# Shining_Pig_9V.net
KiCad netlist of a schematic drawn in Altium Designer
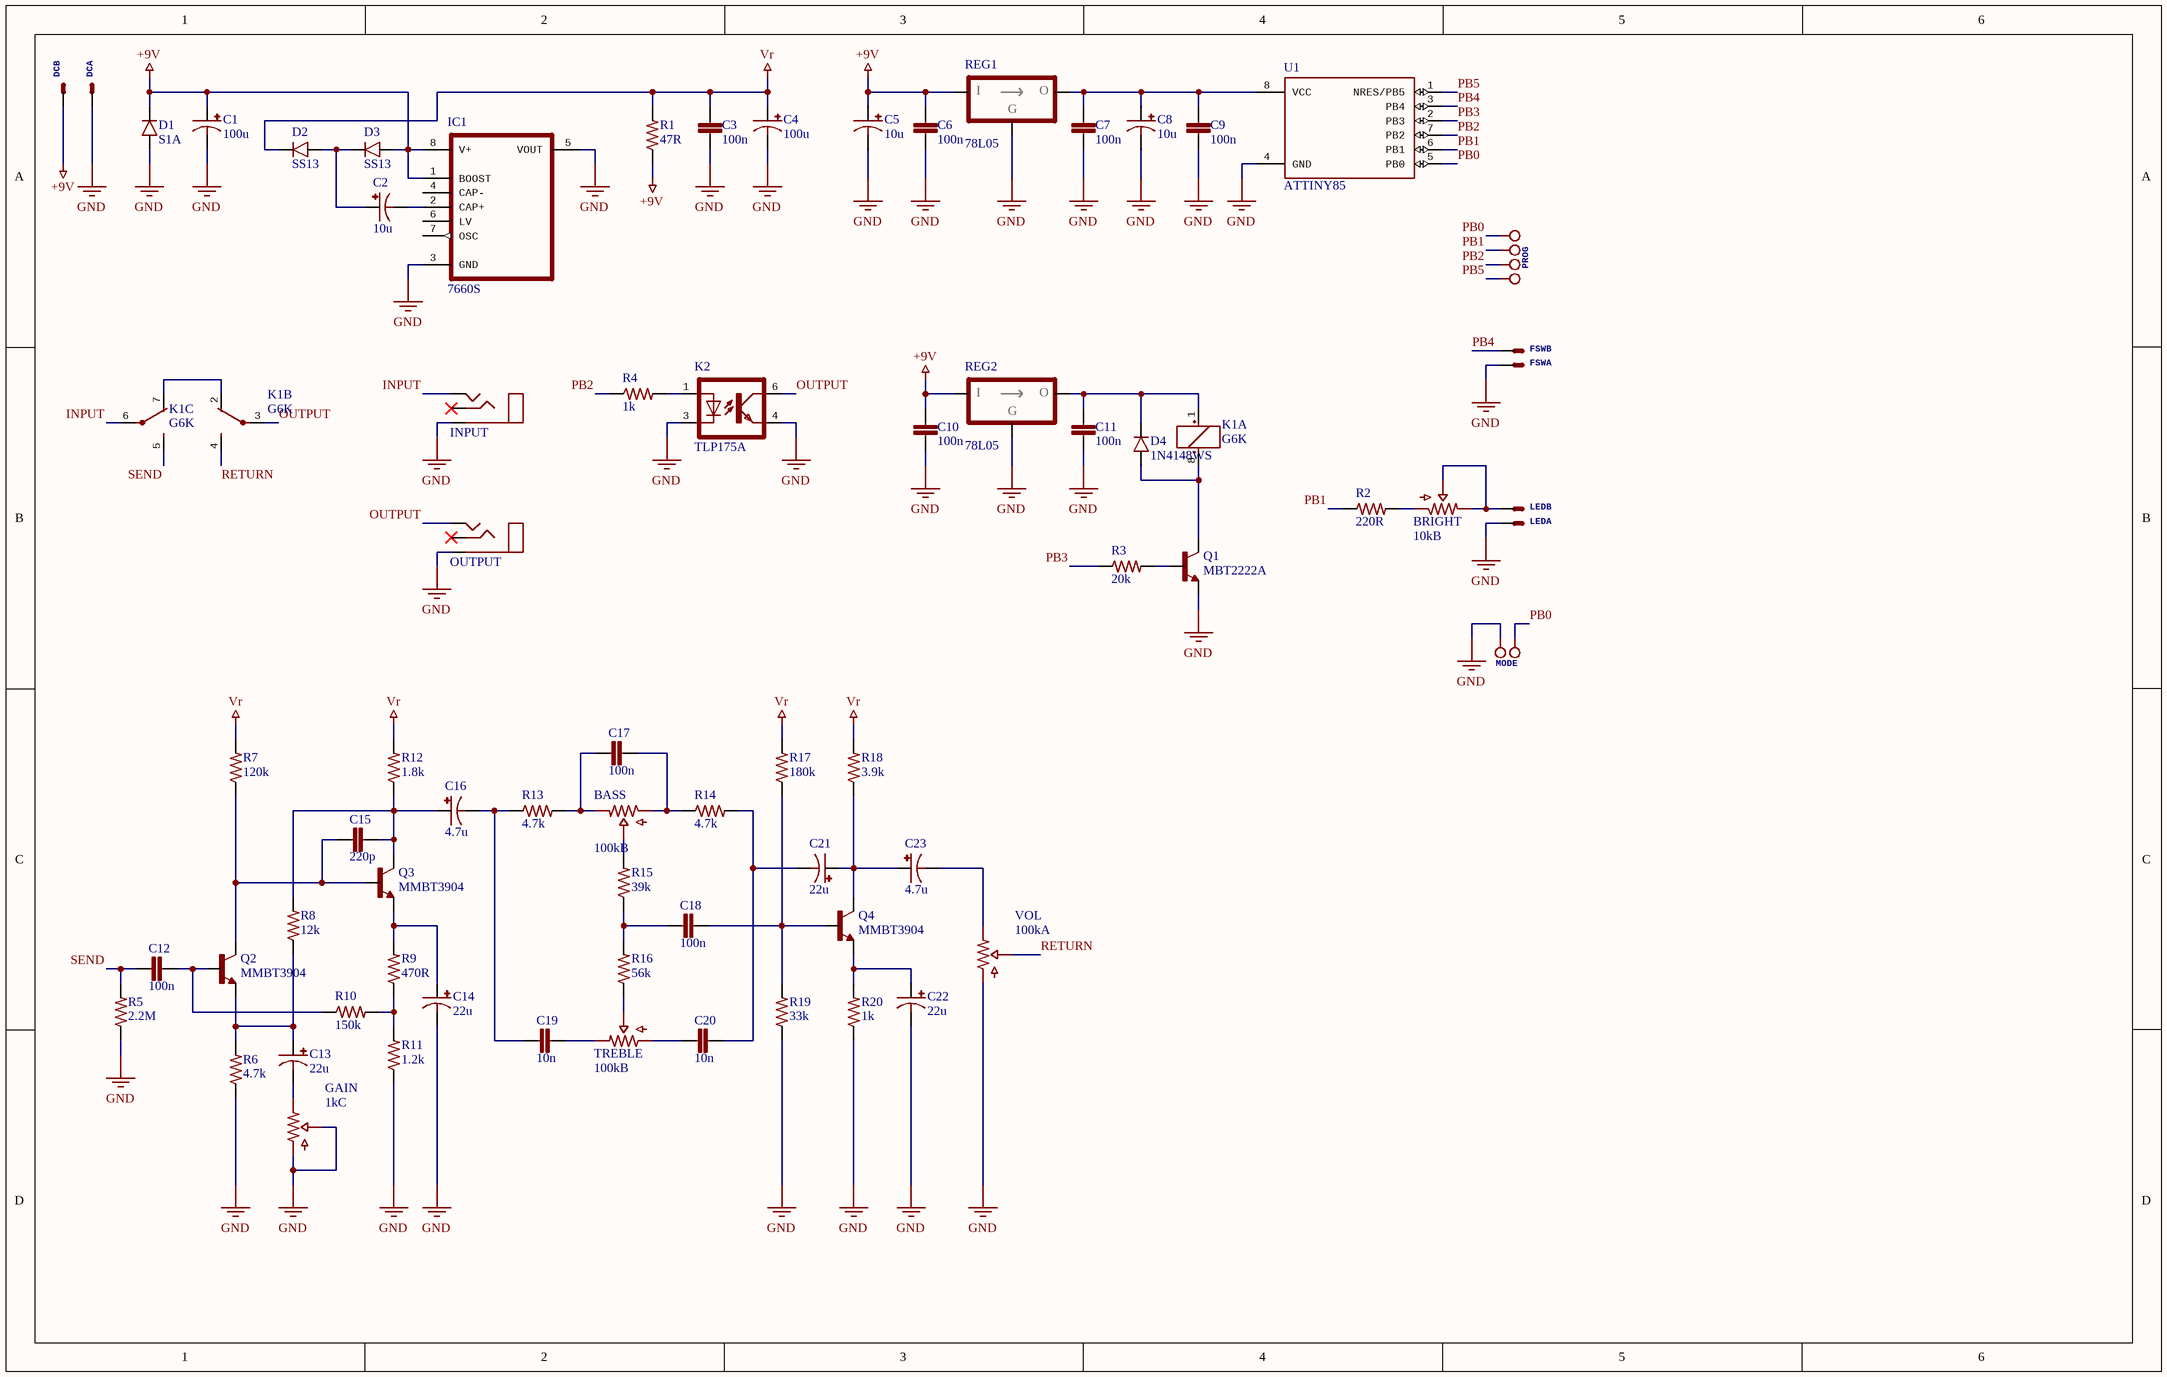
[diagram p0: Shining Pig 9V.SchDoc]

(export (version "E")
  (design (tool "Eeschema 10.0.6"))
  (components
    (comp (ref "BASS")
      (value "100kB")
      (footprint "ALPHA_16mm_BOTTOM")
      (description "100k Lin potentiometer round shaft")
      (libsource (lib "Pedals") (part "POT_100kB_ALPHA_16mm"))
    )
    (comp (ref "BRIGHT")
      (value "10kB")
      (footprint "BOURNS_3362P")
      (description "10k Lin 3362P trimmer")
      (libsource (lib "Pedals") (part "TRIM_10kB_3362P"))
    )
    (comp (ref "C1")
      (value "100u")
      (footprint "CAPAE_D")
      (description "CAP ALUM 100UF 25V SMD")
      (fields
        (field (name "MANUFACTURER") "Multicomp")
        (field (name "MANUFACTURER PART NUMBER") "MCVVT025M101EA6L")
      )
      (libsource (lib "Pedals SMD") (part "MCVVT025M101EA6L"))
    )
    (comp (ref "C2")
      (value "10u")
      (footprint "CAPAE_B")
      (description "CAP ALUM 10UF 25V SMD")
      (fields
        (field (name "MANUFACTURER") "Multicomp")
        (field (name "MANUFACTURER PART NUMBER") "MCVVT025M100CA1L")
      )
      (libsource (lib "") (part "MCVVT025M100CA1L_1"))
    )
    (comp (ref "C3")
      (value "100n")
      (footprint "CHIP_0603")
      (description "CAP CER 100NF 50V X7R 0603")
      (fields
        (field (name "MANUFACTURER") "Multicomp")
        (field (name "MANUFACTURER PART NUMBER") "MC0603B104K500CT")
      )
      (libsource (lib "Pedals SMD") (part "MC0603B104K500CT"))
    )
    (comp (ref "C4")
      (value "100u")
      (footprint "CAPAE_D")
      (description "CAP ALUM 100UF 25V SMD")
      (fields
        (field (name "MANUFACTURER") "Multicomp")
        (field (name "MANUFACTURER PART NUMBER") "MCVVT025M101EA6L")
      )
      (libsource (lib "Pedals SMD") (part "MCVVT025M101EA6L"))
    )
    (comp (ref "C5")
      (value "10u")
      (footprint "CAPAE_B")
      (description "CAP ALUM 10UF 25V SMD")
      (fields
        (field (name "MANUFACTURER") "Multicomp")
        (field (name "MANUFACTURER PART NUMBER") "MCVVT025M100CA1L")
      )
      (libsource (lib "Pedals SMD") (part "MCVVT025M100CA1L"))
    )
    (comp (ref "C6")
      (value "100n")
      (footprint "CHIP_0603")
      (description "CAP CER 100NF 50V X7R 0603")
      (fields
        (field (name "MANUFACTURER") "Multicomp")
        (field (name "MANUFACTURER PART NUMBER") "MC0603B104K500CT")
      )
      (libsource (lib "Pedals SMD") (part "MC0603B104K500CT"))
    )
    (comp (ref "C7")
      (value "100n")
      (footprint "CHIP_0603")
      (description "CAP CER 100NF 50V X7R 0603")
      (fields
        (field (name "MANUFACTURER") "Multicomp")
        (field (name "MANUFACTURER PART NUMBER") "MC0603B104K500CT")
      )
      (libsource (lib "Pedals SMD") (part "MC0603B104K500CT"))
    )
    (comp (ref "C8")
      (value "10u")
      (footprint "CAPAE_B")
      (description "CAP ALUM 10UF 25V SMD")
      (fields
        (field (name "MANUFACTURER") "Multicomp")
        (field (name "MANUFACTURER PART NUMBER") "MCVVT025M100CA1L")
      )
      (libsource (lib "Pedals SMD") (part "MCVVT025M100CA1L"))
    )
    (comp (ref "C9")
      (value "100n")
      (footprint "CHIP_0603")
      (description "CAP CER 100NF 50V X7R 0603")
      (fields
        (field (name "MANUFACTURER") "Multicomp")
        (field (name "MANUFACTURER PART NUMBER") "MC0603B104K500CT")
      )
      (libsource (lib "Pedals SMD") (part "MC0603B104K500CT"))
    )
    (comp (ref "C10")
      (value "100n")
      (footprint "CHIP_0603")
      (description "CAP CER 100NF 50V X7R 0603")
      (fields
        (field (name "MANUFACTURER") "Multicomp")
        (field (name "MANUFACTURER PART NUMBER") "MC0603B104K500CT")
      )
      (libsource (lib "Pedals SMD") (part "MC0603B104K500CT"))
    )
    (comp (ref "C11")
      (value "100n")
      (footprint "CHIP_0603")
      (description "CAP CER 100NF 50V X7R 0603")
      (fields
        (field (name "MANUFACTURER") "Multicomp")
        (field (name "MANUFACTURER PART NUMBER") "MC0603B104K500CT")
      )
      (libsource (lib "Pedals SMD") (part "MC0603B104K500CT"))
    )
    (comp (ref "C12")
      (value "100n")
      (footprint "CHIP_1206")
      (description "CAP CER 100NF 50V C0G/NP0 1206")
      (fields
        (field (name "MANUFACTURER") "Murata")
        (field (name "MANUFACTURER PART NUMBER") "GRM31C5C1H104JA01L")
      )
      (libsource (lib "Pedals SMD") (part "GRM31C5C1H104JA01L"))
    )
    (comp (ref "C13")
      (value "22u")
      (footprint "CAPAE_D")
      (description "CAP ALUM 22UF 20% 35V LESR SMD")
      (fields
        (field (name "MANUFACTURER") "Panasonic")
        (field (name "MANUFACTURER PART NUMBER") "EEEFC1V220AP")
      )
      (libsource (lib "Pedals SMD") (part "EEEFC1V220AP"))
    )
    (comp (ref "C14")
      (value "22u")
      (footprint "CAPAE_D")
      (description "CAP ALUM 22UF 20% 35V LESR SMD")
      (fields
        (field (name "MANUFACTURER") "Panasonic")
        (field (name "MANUFACTURER PART NUMBER") "EEEFC1V220AP")
      )
      (libsource (lib "Pedals SMD") (part "EEEFC1V220AP"))
    )
    (comp (ref "C15")
      (value "220p")
      (footprint "CHIP_0603")
      (description "CAP CER 220PF 50V C0G/NP0 0603")
      (fields
        (field (name "MANUFACTURER") "Multicomp")
        (field (name "MANUFACTURER PART NUMBER") "MC0603N221J500CT")
      )
      (libsource (lib "Pedals SMD") (part "MC0603N221J500CT"))
    )
    (comp (ref "C16")
      (value "4.7u")
      (footprint "CAPAE_C")
      (description "CAP ALUM 4.7UF 50V LESR SMD")
      (fields
        (field (name "MANUFACTURER") "Panasonic")
        (field (name "MANUFACTURER PART NUMBER") "EEEFC1H4R7R")
      )
      (libsource (lib "Pedals SMD") (part "EEEFC1H4R7R"))
    )
    (comp (ref "C17")
      (value "100n")
      (footprint "CHIP_1206")
      (description "CAP CER 100NF 50V C0G/NP0 1206")
      (fields
        (field (name "MANUFACTURER") "Murata")
        (field (name "MANUFACTURER PART NUMBER") "GRM31C5C1H104JA01L")
      )
      (libsource (lib "Pedals SMD") (part "GRM31C5C1H104JA01L"))
    )
    (comp (ref "C18")
      (value "100n")
      (footprint "CHIP_1206")
      (description "CAP CER 100NF 50V C0G/NP0 1206")
      (fields
        (field (name "MANUFACTURER") "Murata")
        (field (name "MANUFACTURER PART NUMBER") "GRM31C5C1H104JA01L")
      )
      (libsource (lib "Pedals SMD") (part "GRM31C5C1H104JA01L"))
    )
    (comp (ref "C19")
      (value "10n")
      (footprint "CHIP_0603")
      (description "CAP CER 10NF 50V C0G/NP0 0603")
      (fields
        (field (name "MANUFACTURER") "Murata")
        (field (name "MANUFACTURER PART NUMBER") "GRM1885C1H103JA01D")
      )
      (libsource (lib "Pedals SMD") (part "GRM1885C1H103JA01D"))
    )
    (comp (ref "C20")
      (value "10n")
      (footprint "CHIP_0603")
      (description "CAP CER 10NF 50V C0G/NP0 0603")
      (fields
        (field (name "MANUFACTURER") "Murata")
        (field (name "MANUFACTURER PART NUMBER") "GRM1885C1H103JA01D")
      )
      (libsource (lib "Pedals SMD") (part "GRM1885C1H103JA01D"))
    )
    (comp (ref "C21")
      (value "22u")
      (footprint "CAPAE_D")
      (description "CAP ALUM 22UF 20% 35V LESR SMD")
      (fields
        (field (name "MANUFACTURER") "Panasonic")
        (field (name "MANUFACTURER PART NUMBER") "EEEFC1V220AP")
      )
      (libsource (lib "") (part "EEEFC1V220AP_1"))
    )
    (comp (ref "C22")
      (value "22u")
      (footprint "CAPAE_D")
      (description "CAP ALUM 22UF 20% 35V LESR SMD")
      (fields
        (field (name "MANUFACTURER") "Panasonic")
        (field (name "MANUFACTURER PART NUMBER") "EEEFC1V220AP")
      )
      (libsource (lib "Pedals SMD") (part "EEEFC1V220AP"))
    )
    (comp (ref "C23")
      (value "4.7u")
      (footprint "CAPAE_C")
      (description "CAP ALUM 4.7UF 50V LESR SMD")
      (fields
        (field (name "MANUFACTURER") "Panasonic")
        (field (name "MANUFACTURER PART NUMBER") "EEEFC1H4R7R")
      )
      (libsource (lib "Pedals SMD") (part "EEEFC1H4R7R"))
    )
    (comp (ref "D1")
      (value "S1A")
      (footprint "DO214")
      (description "DIODE GEN PURP 50V 1A SMA")
      (fields (field (name "MANUFACTURER") "ON Semiconductor / Fairchild"))
      (libsource (lib "Pedals SMD") (part "S1A"))
    )
    (comp (ref "D2")
      (value "SS13")
      (footprint "SOD123F")
      (description "DIODE SCHOTTKY 30V 1A SOD123F")
      (fields
        (field (name "MANUFACTURER") "ON Semiconductor / Fairchild")
        (field (name "MANUFACTURER PART NUMBER") "SS13FL")
      )
      (libsource (lib "Pedals SMD") (part "SS13FL"))
    )
    (comp (ref "D3")
      (value "SS13")
      (footprint "SOD123F")
      (description "DIODE SCHOTTKY 30V 1A SOD123F")
      (fields
        (field (name "MANUFACTURER") "ON Semiconductor / Fairchild")
        (field (name "MANUFACTURER PART NUMBER") "SS13FL")
      )
      (libsource (lib "Pedals SMD") (part "SS13FL"))
    )
    (comp (ref "D4")
      (value "1N4148WS")
      (footprint "SOD323")
      (description "DIODE GEN PURP 75V 150MA SOD323F")
      (fields (field (name "MANUFACTURER") "ON Semiconductor / Fairchild"))
      (libsource (lib "Pedals SMD") (part "1N4148WS"))
    )
    (comp (ref "DC")
      (value "J_JST-XH-02")
      (footprint "JST-XH-02")
      (description "2 Pins male XH header")
      (libsource (lib "Pedals") (part "J_JST-XH-02"))
    )
    (comp (ref "FSW")
      (value "J_JST-XH-02")
      (footprint "JST-XH-02")
      (description "2 Pins male XH header")
      (libsource (lib "Pedals") (part "J_JST-XH-02"))
    )
    (comp (ref "GAIN")
      (value "1kC")
      (footprint "ALPHA_16mm_BOTTOM")
      (description "1k Reverse log potentiometer round shaft")
      (libsource (lib "Pedals") (part "POT_1kC_ALPHA_16mm"))
    )
    (comp (ref "IC1")
      (value "7660S")
      (footprint "SO8")
      (description "RENESAS - ICL7660SCBAZ - IC DC DC CHARGE PUMP")
      (fields
        (field (name "MANUFACTURER") "Intersil")
        (field (name "MANUFACTURER PART NUMBER") "ICL7660SCBAZ")
      )
      (libsource (lib "Pedals SMD") (part "ICL7660SCBAZ"))
    )
    (comp (ref "INPUT")
      (value "J_STEREO")
      (footprint "STEREO")
      (description "6.35mm stereo insulated socket jack PCB mounted")
      (libsource (lib "Pedals") (part "J_STEREO"))
    )
    (comp (ref "K1")
      (value "G6K")
      (footprint "G6K")
      (description "OMRON - G6K-2F 5DC - RELAY, SIGNAL, DPDT, 30VDC, 1A")
      (fields (field (name "MANUFACTURER") "Cliff") (field (name "MANUFACTURER PART NUMBER") "G6K-2F5DC"))
      (libsource (lib "") (part "G6K-2F5DC_1"))
    )
    (comp (ref "K2")
      (value "TLP175A")
      (footprint "TLP175A")
      (description "Toshiba TLP175A AC Input MOSFET Output Optocoupler, Surface Mount, 4-Pin SOIC")
      (fields (field (name "MANUFACTURER") "Toshiba"))
      (libsource (lib "Pedals SMD") (part "TLP175A"))
    )
    (comp (ref "LED")
      (value "J_JST-XH-02")
      (footprint "JST-XH-02")
      (description "2 Pins male XH header")
      (libsource (lib "Pedals") (part "J_JST-XH-02"))
    )
    (comp (ref "MODE")
      (value "J_HEADER_2PINS")
      (footprint "HEADER_2PINS")
      (description "2 Pins male header")
      (libsource (lib "Pedals") (part "J_HEADER_2PINS"))
    )
    (comp (ref "OUTPUT")
      (value "J_STEREO")
      (footprint "STEREO")
      (description "6.35mm stereo insulated socket jack PCB mounted")
      (libsource (lib "Pedals") (part "J_STEREO"))
    )
    (comp (ref "PROG")
      (value "J_HEADER_4PINS_FEM")
      (footprint "HEADER_4Pins_FEM")
      (description "4 Pins female header")
      (libsource (lib "Pedals") (part "J_HEADER_4PINS_FEM"))
    )
    (comp (ref "Q1")
      (value "MBT2222A")
      (footprint "SOT323")
      (description "TRANS NPN 40V 0.6A SOT323")
      (fields
        (field (name "MANUFACTURER") "ON Semiconductor")
        (field (name "MANUFACTURER PART NUMBER") "MMBT2222AWT1G")
      )
      (libsource (lib "Pedals SMD") (part "MMBT2222AWT1G"))
    )
    (comp (ref "Q2")
      (value "MMBT3904")
      (footprint "SOT23")
      (description "TRANS NPN 40V 0.2A SOT23")
      (fields
        (field (name "MANUFACTURER") "ON Semiconductor")
        (field (name "MANUFACTURER PART NUMBER") "MMBT3904LT1G")
      )
      (libsource (lib "Pedals SMD") (part "MMBT3904LT1G"))
    )
    (comp (ref "Q3")
      (value "MMBT3904")
      (footprint "SOT23")
      (description "TRANS NPN 40V 0.2A SOT23")
      (fields
        (field (name "MANUFACTURER") "ON Semiconductor")
        (field (name "MANUFACTURER PART NUMBER") "MMBT3904LT1G")
      )
      (libsource (lib "Pedals SMD") (part "MMBT3904LT1G"))
    )
    (comp (ref "Q4")
      (value "MMBT3904")
      (footprint "SOT23")
      (description "TRANS NPN 40V 0.2A SOT23")
      (fields
        (field (name "MANUFACTURER") "ON Semiconductor")
        (field (name "MANUFACTURER PART NUMBER") "MMBT3904LT1G")
      )
      (libsource (lib "Pedals SMD") (part "MMBT3904LT1G"))
    )
    (comp (ref "R1")
      (value "47R")
      (footprint "CHIP_R_1206")
      (description "RES SMD 47 OHM 1% 1/4W 1206")
      (fields
        (field (name "MANUFACTURER") "Vishay")
        (field (name "MANUFACTURER PART NUMBER") "CRCW120647R0FKEA")
      )
      (libsource (lib "Pedals SMD") (part "CRCW120647R0FKEA"))
    )
    (comp (ref "R2")
      (value "220R")
      (footprint "CHIP_R_1206")
      (description "RES SMD 220 OHM 1% 1/4W 1206")
      (fields
        (field (name "MANUFACTURER") "Vishay")
        (field (name "MANUFACTURER PART NUMBER") "CRCW1206220RFKEA")
      )
      (libsource (lib "Pedals SMD") (part "CRCW1206220RFKEA"))
    )
    (comp (ref "R3")
      (value "20k")
      (footprint "CHIP_R_0603")
      (description "RES SMD 20K OHM 1% 1/10W 0603")
      (fields
        (field (name "MANUFACTURER") "Vishay")
        (field (name "MANUFACTURER PART NUMBER") "CRCW060320K0FKEA")
      )
      (libsource (lib "Pedals SMD") (part "CRCW060320K0FKEA"))
    )
    (comp (ref "R4")
      (value "1k")
      (footprint "CHIP_R_0603")
      (description "RES SMD 1K OHM 1% 1/10W 0603")
      (fields
        (field (name "MANUFACTURER") "Vishay Dale")
        (field (name "MANUFACTURER PART NUMBER") "CRCW06031K00FKEA")
      )
      (libsource (lib "Pedals SMD") (part "CRCW06031K00FKEA"))
    )
    (comp (ref "R5")
      (value "2.2M")
      (footprint "CHIP_R_0603")
      (description "RES SMD 2.2M OHM 1% 1/10W 0603")
      (fields
        (field (name "MANUFACTURER") "Vishay")
        (field (name "MANUFACTURER PART NUMBER") "CRCW06032M20FKEA")
      )
      (libsource (lib "Pedals SMD") (part "CRCW06032M20FKEA"))
    )
    (comp (ref "R6")
      (value "4.7k")
      (footprint "CHIP_R_0603")
      (description "RES SMD 4.7K OHM 1% 1/10W 0603")
      (fields
        (field (name "MANUFACTURER") "Vishay")
        (field (name "MANUFACTURER PART NUMBER") "CRCW06034K70FKEA")
      )
      (libsource (lib "Pedals SMD") (part "CRCW06034K70FKEA"))
    )
    (comp (ref "R7")
      (value "120k")
      (footprint "CHIP_R_1206")
      (description "RES SMD 120K OHM 1% 1/4W 1206")
      (fields
        (field (name "MANUFACTURER") "Vishay")
        (field (name "MANUFACTURER PART NUMBER") "CRCW1206120KFKEA")
      )
      (libsource (lib "Pedals SMD") (part "CRCW1206120KFKEA"))
    )
    (comp (ref "R8")
      (value "12k")
      (footprint "CHIP_R_0603")
      (description "RES SMD 12K OHM 1% 1/10W 0603")
      (fields
        (field (name "MANUFACTURER") "Vishay")
        (field (name "MANUFACTURER PART NUMBER") "CRCW060312K0FKEA")
      )
      (libsource (lib "Pedals SMD") (part "CRCW060312K0FKEA"))
    )
    (comp (ref "R9")
      (value "470R")
      (footprint "CHIP_R_0603")
      (description "RES SMD 470 OHM 1% 1/10W 0603")
      (fields
        (field (name "MANUFACTURER") "Vishay")
        (field (name "MANUFACTURER PART NUMBER") "CRCW0603470RFKEA")
      )
      (libsource (lib "Pedals SMD") (part "CRCW0603470RFKEA"))
    )
    (comp (ref "R10")
      (value "150k")
      (footprint "CHIP_R_0603")
      (description "RES SMD 150K OHM 1% 1/10W 0603")
      (fields
        (field (name "MANUFACTURER") "Vishay")
        (field (name "MANUFACTURER PART NUMBER") "CRCW0603150KFKEA")
      )
      (libsource (lib "Pedals SMD") (part "CRCW0603150KFKEA"))
    )
    (comp (ref "R11")
      (value "1.2k")
      (footprint "CHIP_R_0603")
      (description "RES SMD 1.2K OHM 1% 1/10W 0603")
      (fields
        (field (name "MANUFACTURER") "Vishay")
        (field (name "MANUFACTURER PART NUMBER") "CRCW06031K20FKEA")
      )
      (libsource (lib "Pedals SMD") (part "CRCW06031K20FKEA"))
    )
    (comp (ref "R12")
      (value "1.8k")
      (footprint "CHIP_R_1206")
      (description "RES SMD 1.8K OHM 1% 1/4W 1206")
      (fields
        (field (name "MANUFACTURER") "Vishay")
        (field (name "MANUFACTURER PART NUMBER") "CRCW12061K80FKEA")
      )
      (libsource (lib "Pedals SMD") (part "CRCW12061K80FKEA"))
    )
    (comp (ref "R13")
      (value "4.7k")
      (footprint "CHIP_R_0603")
      (description "RES SMD 4.7K OHM 1% 1/10W 0603")
      (fields
        (field (name "MANUFACTURER") "Vishay")
        (field (name "MANUFACTURER PART NUMBER") "CRCW06034K70FKEA")
      )
      (libsource (lib "Pedals SMD") (part "CRCW06034K70FKEA"))
    )
    (comp (ref "R14")
      (value "4.7k")
      (footprint "CHIP_R_0603")
      (description "RES SMD 4.7K OHM 1% 1/10W 0603")
      (fields
        (field (name "MANUFACTURER") "Vishay")
        (field (name "MANUFACTURER PART NUMBER") "CRCW06034K70FKEA")
      )
      (libsource (lib "Pedals SMD") (part "CRCW06034K70FKEA"))
    )
    (comp (ref "R15")
      (value "39k")
      (footprint "CHIP_R_0603")
      (description "RES SMD 39K OHM 1% 1/10W 0603")
      (fields
        (field (name "MANUFACTURER") "Vishay")
        (field (name "MANUFACTURER PART NUMBER") "CRCW060339K0FKEA")
      )
      (libsource (lib "Pedals SMD") (part "CRCW060339K0FKEA"))
    )
    (comp (ref "R16")
      (value "56k")
      (footprint "CHIP_R_0603")
      (description "RES SMD 5.6K OHM 1% 1/10W 0603")
      (fields
        (field (name "MANUFACTURER") "Vishay")
        (field (name "MANUFACTURER PART NUMBER") "CRCW06035K60FKEA")
      )
      (libsource (lib "Pedals SMD") (part "CRCW06035K60FKEA"))
    )
    (comp (ref "R17")
      (value "180k")
      (footprint "CHIP_R_1206")
      (description "RES SMD 180K OHM 1% 1/4W 1206")
      (fields
        (field (name "MANUFACTURER") "Vishay")
        (field (name "MANUFACTURER PART NUMBER") "CRCW1206180KFKEA")
      )
      (libsource (lib "Pedals SMD") (part "CRCW1206180KFKEA"))
    )
    (comp (ref "R18")
      (value "3.9k")
      (footprint "CHIP_R_1206")
      (description "RES SMD 3.9K OHM 1% 1/4W 1206")
      (fields
        (field (name "MANUFACTURER") "Vishay")
        (field (name "MANUFACTURER PART NUMBER") "CRCW12063K90FKEA")
      )
      (libsource (lib "Pedals SMD") (part "CRCW12063K90FKEA"))
    )
    (comp (ref "R19")
      (value "33k")
      (footprint "CHIP_R_0603")
      (description "RES SMD 33K OHM 1% 1/10W 0603")
      (fields
        (field (name "MANUFACTURER") "Vishay")
        (field (name "MANUFACTURER PART NUMBER") "CRCW060333K0FKEA")
      )
      (libsource (lib "Pedals SMD") (part "CRCW060333K0FKEA"))
    )
    (comp (ref "R20")
      (value "1k")
      (footprint "CHIP_R_0603")
      (description "RES SMD 1K OHM 1% 1/10W 0603")
      (fields
        (field (name "MANUFACTURER") "Vishay Dale")
        (field (name "MANUFACTURER PART NUMBER") "CRCW06031K00FKEA")
      )
      (libsource (lib "Pedals SMD") (part "CRCW06031K00FKEA"))
    )
    (comp (ref "REG1")
      (value "78L05")
      (footprint "SOT23-3")
      (description "TAIWAN SEMICONDUCTOR - TS78L05CX RFG - REG 3-TERMINAL 100MA, SMD, SOT23-3")
      (fields
        (field (name "MANUFACTURER") "Taiwan Semiconductor")
        (field (name "MANUFACTURER PART NUMBER") "TS78L05CXRFG")
      )
      (libsource (lib "Pedals SMD") (part "TS78L05CXRFG"))
    )
    (comp (ref "REG2")
      (value "78L05")
      (footprint "SOT23-3")
      (description "TAIWAN SEMICONDUCTOR - TS78L05CX RFG - REG 3-TERMINAL 100MA, SMD, SOT23-3")
      (fields
        (field (name "MANUFACTURER") "Taiwan Semiconductor")
        (field (name "MANUFACTURER PART NUMBER") "TS78L05CXRFG")
      )
      (libsource (lib "Pedals SMD") (part "TS78L05CXRFG"))
    )
    (comp (ref "TREBLE")
      (value "100kB")
      (footprint "ALPHA_16mm_BOTTOM")
      (description "100k Lin potentiometer round shaft")
      (libsource (lib "Pedals") (part "POT_100kB_ALPHA_16mm"))
    )
    (comp (ref "U1")
      (value "ATTINY85")
      (footprint "SOP8")
      (description "IC, 8BIT MCU, AVR TINY, 20MHZ, 8-SOIC")
      (fields
        (field (name "MANUFACTURER") "Microchip / Atmel")
        (field (name "MANUFACTURER PART NUMBER") "ATTINY85-20SU")
      )
      (libsource (lib "Pedals SMD") (part "ATTINY85-20SU"))
    )
    (comp (ref "VOL")
      (value "100kA")
      (footprint "ALPHA_16mm_BOTTOM")
      (description "100k Log potentiometer round shaft")
      (libsource (lib "Pedals") (part "POT_100kA_ALPHA_16mm"))
    )
  )
  (nets
    (net (code "1") (name "+9V") (class "Default")
      (node (ref "C1") (pin "+") (pinfunction "+_+") (pintype "passive"))
      (node (ref "C10") (pin "1") (pinfunction "1_1") (pintype "passive"))
      (node (ref "C5") (pin "+") (pinfunction "+_+") (pintype "passive"))
      (node (ref "C6") (pin "1") (pinfunction "1_1") (pintype "passive"))
      (node (ref "D1") (pin "1") (pinfunction "1_1") (pintype "passive"))
      (node (ref "D3") (pin "2") (pinfunction "2_2") (pintype "passive"))
      (node (ref "DC") (pin "1") (pinfunction "S_1") (pintype "passive"))
      (node (ref "IC1") (pin "1") (pinfunction "BOOST_1") (pintype "power_in"))
      (node (ref "IC1") (pin "8") (pinfunction "V+_8") (pintype "power_in"))
      (node (ref "R1") (pin "1") (pinfunction "1_1") (pintype "passive"))
      (node (ref "REG1") (pin "2") (pinfunction "INPUT_2") (pintype "power_in"))
      (node (ref "REG2") (pin "2") (pinfunction "INPUT_2") (pintype "power_in"))
    )
    (net (code "2") (name "/INPUT") (class "Default")
      (node (ref "INPUT") (pin "T") (pinfunction "T_T") (pintype "passive"))
      (node (ref "K1") (pin "6") (pinfunction "P_6") (pintype "passive"))
    )
    (net (code "3") (name "/OUTPUT") (class "Default")
      (node (ref "K1") (pin "3") (pinfunction "P_3") (pintype "passive"))
      (node (ref "K2") (pin "6") (pinfunction "COL_6") (pintype "passive"))
      (node (ref "OUTPUT") (pin "T") (pinfunction "T_T") (pintype "passive"))
    )
    (net (code "4") (name "/PB0") (class "Default")
      (node (ref "MODE") (pin "2") (pinfunction "2_2") (pintype "passive"))
      (node (ref "PROG") (pin "4") (pinfunction "4_4") (pintype "passive"))
      (node (ref "U1") (pin "5") (pinfunction "PB0_5") (pintype "bidirectional"))
    )
    (net (code "5") (name "/PB1") (class "Default")
      (node (ref "PROG") (pin "3") (pinfunction "3_3") (pintype "passive"))
      (node (ref "R2") (pin "1") (pinfunction "1_1") (pintype "passive"))
      (node (ref "U1") (pin "6") (pinfunction "PB1_6") (pintype "bidirectional"))
    )
    (net (code "6") (name "/PB2") (class "Default")
      (node (ref "PROG") (pin "2") (pinfunction "2_2") (pintype "passive"))
      (node (ref "R4") (pin "1") (pinfunction "1_1") (pintype "passive"))
      (node (ref "U1") (pin "7") (pinfunction "PB2_7") (pintype "bidirectional"))
    )
    (net (code "7") (name "/PB3") (class "Default")
      (node (ref "R3") (pin "1") (pinfunction "1_1") (pintype "passive"))
      (node (ref "U1") (pin "2") (pinfunction "PB3_2") (pintype "bidirectional"))
    )
    (net (code "8") (name "/PB4") (class "Default")
      (node (ref "FSW") (pin "1") (pinfunction "S_1") (pintype "passive"))
      (node (ref "U1") (pin "3") (pinfunction "PB4_3") (pintype "bidirectional"))
    )
    (net (code "9") (name "/PB5") (class "Default")
      (node (ref "PROG") (pin "1") (pinfunction "1_1") (pintype "passive"))
      (node (ref "U1") (pin "1") (pinfunction "NRES/PB5_1") (pintype "bidirectional"))
    )
    (net (code "10") (name "/RETURN") (class "Default")
      (node (ref "K1") (pin "4") (pinfunction "S_4") (pintype "passive"))
      (node (ref "VOL") (pin "2") (pinfunction "2_2") (pintype "passive"))
    )
    (net (code "11") (name "/SEND") (class "Default")
      (node (ref "C12") (pin "2") (pinfunction "2_2") (pintype "passive"))
      (node (ref "K1") (pin "5") (pinfunction "S_5") (pintype "passive"))
      (node (ref "R5") (pin "2") (pinfunction "2_2") (pintype "passive"))
    )
    (net (code "12") (name "GND") (class "Default")
      (node (ref "C1") (pin "-") (pinfunction "-_-") (pintype "passive"))
      (node (ref "C10") (pin "2") (pinfunction "2_2") (pintype "passive"))
      (node (ref "C11") (pin "2") (pinfunction "2_2") (pintype "passive"))
      (node (ref "C14") (pin "-") (pinfunction "-_-") (pintype "passive"))
      (node (ref "C22") (pin "-") (pinfunction "-_-") (pintype "passive"))
      (node (ref "C3") (pin "2") (pinfunction "2_2") (pintype "passive"))
      (node (ref "C4") (pin "-") (pinfunction "-_-") (pintype "passive"))
      (node (ref "C5") (pin "-") (pinfunction "-_-") (pintype "passive"))
      (node (ref "C6") (pin "2") (pinfunction "2_2") (pintype "passive"))
      (node (ref "C7") (pin "2") (pinfunction "2_2") (pintype "passive"))
      (node (ref "C8") (pin "-") (pinfunction "-_-") (pintype "passive"))
      (node (ref "C9") (pin "2") (pinfunction "2_2") (pintype "passive"))
      (node (ref "D1") (pin "2") (pinfunction "2_2") (pintype "passive"))
      (node (ref "DC") (pin "2") (pinfunction "S_2") (pintype "passive"))
      (node (ref "FSW") (pin "2") (pinfunction "S_2") (pintype "passive"))
      (node (ref "GAIN") (pin "1") (pinfunction "1_1") (pintype "passive"))
      (node (ref "GAIN") (pin "2") (pinfunction "2_2") (pintype "passive"))
      (node (ref "IC1") (pin "3") (pinfunction "GND_3") (pintype "power_in"))
      (node (ref "IC1") (pin "5") (pinfunction "VOUT_5") (pintype "power_in"))
      (node (ref "INPUT") (pin "S") (pinfunction "S_S") (pintype "passive"))
      (node (ref "K2") (pin "3") (pinfunction "C_3") (pintype "passive"))
      (node (ref "K2") (pin "4") (pinfunction "EMIT_4") (pintype "passive"))
      (node (ref "LED") (pin "2") (pinfunction "S_2") (pintype "passive"))
      (node (ref "MODE") (pin "1") (pinfunction "1_1") (pintype "passive"))
      (node (ref "OUTPUT") (pin "S") (pinfunction "S_S") (pintype "passive"))
      (node (ref "Q1") (pin "2") (pinfunction "E_2") (pintype "passive"))
      (node (ref "R11") (pin "1") (pinfunction "1_1") (pintype "passive"))
      (node (ref "R19") (pin "1") (pinfunction "1_1") (pintype "passive"))
      (node (ref "R20") (pin "1") (pinfunction "1_1") (pintype "passive"))
      (node (ref "R5") (pin "1") (pinfunction "1_1") (pintype "passive"))
      (node (ref "R6") (pin "1") (pinfunction "1_1") (pintype "passive"))
      (node (ref "REG1") (pin "3") (pinfunction "COMMON_3") (pintype "power_in"))
      (node (ref "REG2") (pin "3") (pinfunction "COMMON_3") (pintype "power_in"))
      (node (ref "U1") (pin "4") (pinfunction "GND_4") (pintype "power_in"))
      (node (ref "VOL") (pin "1") (pinfunction "1_1") (pintype "passive"))
    )
    (net (code "13") (name "Net-(BASS-Pad1)") (class "Default")
      (node (ref "BASS") (pin "1") (pinfunction "1_1") (pintype "passive"))
      (node (ref "C17") (pin "1") (pinfunction "1_1") (pintype "passive"))
      (node (ref "R14") (pin "1") (pinfunction "1_1") (pintype "passive"))
    )
    (net (code "14") (name "Net-(BASS-Pad2)") (class "Default")
      (node (ref "BASS") (pin "2") (pinfunction "2_2") (pintype "passive"))
      (node (ref "R15") (pin "2") (pinfunction "2_2") (pintype "passive"))
    )
    (net (code "15") (name "Net-(BASS-Pad3)") (class "Default")
      (node (ref "BASS") (pin "3") (pinfunction "3_3") (pintype "passive"))
      (node (ref "C17") (pin "2") (pinfunction "2_2") (pintype "passive"))
      (node (ref "R13") (pin "2") (pinfunction "2_2") (pintype "passive"))
    )
    (net (code "16") (name "Net-(BRIGHT-Pad1)") (class "Default")
      (node (ref "BRIGHT") (pin "1") (pinfunction "1_1") (pintype "passive"))
      (node (ref "R2") (pin "2") (pinfunction "2_2") (pintype "passive"))
    )
    (net (code "17") (name "Net-(C2-Pad+)") (class "Default")
      (node (ref "C2") (pin "+") (pinfunction "+_+") (pintype "passive"))
      (node (ref "D2") (pin "2") (pinfunction "2_2") (pintype "passive"))
      (node (ref "D3") (pin "1") (pinfunction "1_1") (pintype "passive"))
    )
    (net (code "18") (name "Net-(C13-Pad-)") (class "Default")
      (node (ref "C13") (pin "-") (pinfunction "-_-") (pintype "passive"))
      (node (ref "GAIN") (pin "3") (pinfunction "3_3") (pintype "passive"))
    )
    (net (code "19") (name "Net-(C16-Pad-)") (class "Default")
      (node (ref "C16") (pin "-") (pinfunction "-_-") (pintype "passive"))
      (node (ref "C19") (pin "2") (pinfunction "2_2") (pintype "passive"))
      (node (ref "R13") (pin "1") (pinfunction "1_1") (pintype "passive"))
    )
    (net (code "20") (name "Net-(C18-Pad2)") (class "Default")
      (node (ref "C18") (pin "2") (pinfunction "2_2") (pintype "passive"))
      (node (ref "R15") (pin "1") (pinfunction "1_1") (pintype "passive"))
      (node (ref "R16") (pin "2") (pinfunction "2_2") (pintype "passive"))
    )
    (net (code "21") (name "Net-(C19-Pad1)") (class "Default")
      (node (ref "C19") (pin "1") (pinfunction "1_1") (pintype "passive"))
      (node (ref "TREBLE") (pin "3") (pinfunction "3_3") (pintype "passive"))
    )
    (net (code "22") (name "Net-(C20-Pad1)") (class "Default")
      (node (ref "C20") (pin "1") (pinfunction "1_1") (pintype "passive"))
      (node (ref "C21") (pin "-") (pinfunction "-_-") (pintype "passive"))
      (node (ref "R14") (pin "2") (pinfunction "2_2") (pintype "passive"))
    )
    (net (code "23") (name "Net-(C20-Pad2)") (class "Default")
      (node (ref "C20") (pin "2") (pinfunction "2_2") (pintype "passive"))
      (node (ref "TREBLE") (pin "1") (pinfunction "1_1") (pintype "passive"))
    )
    (net (code "24") (name "Net-(C23-Pad-)") (class "Default")
      (node (ref "C23") (pin "-") (pinfunction "-_-") (pintype "passive"))
      (node (ref "VOL") (pin "3") (pinfunction "3_3") (pintype "passive"))
    )
    (net (code "25") (name "Net-(IC1-CAP+)") (class "Default")
      (node (ref "C2") (pin "-") (pinfunction "-_-") (pintype "passive"))
      (node (ref "IC1") (pin "2") (pinfunction "CAP+_2") (pintype "passive"))
    )
    (net (code "26") (name "Net-(K1A-+)") (class "Default")
      (node (ref "C11") (pin "1") (pinfunction "1_1") (pintype "passive"))
      (node (ref "D4") (pin "1") (pinfunction "1_1") (pintype "passive"))
      (node (ref "K1") (pin "1") (pinfunction "+_1") (pintype "passive"))
      (node (ref "REG2") (pin "1") (pinfunction "OUTPUT_1") (pintype "power_in"))
    )
    (net (code "27") (name "Net-(K1A--)") (class "Default")
      (node (ref "D4") (pin "2") (pinfunction "2_2") (pintype "passive"))
      (node (ref "K1") (pin "8") (pinfunction "-_8") (pintype "passive"))
      (node (ref "Q1") (pin "3") (pinfunction "C_3") (pintype "passive"))
    )
    (net (code "28") (name "Net-(K1B-O)") (class "Default")
      (node (ref "K1") (pin "2") (pinfunction "O_2") (pintype "passive"))
      (node (ref "K1") (pin "7") (pinfunction "O_7") (pintype "passive"))
    )
    (net (code "29") (name "Net-(K2-A)") (class "Default")
      (node (ref "K2") (pin "1") (pinfunction "A_1") (pintype "passive"))
      (node (ref "R4") (pin "2") (pinfunction "2_2") (pintype "passive"))
    )
    (net (code "30") (name "Net-(LEDB-S)") (class "Default")
      (node (ref "BRIGHT") (pin "2") (pinfunction "2_2") (pintype "passive"))
      (node (ref "BRIGHT") (pin "3") (pinfunction "3_3") (pintype "passive"))
      (node (ref "LED") (pin "1") (pinfunction "S_1") (pintype "passive"))
    )
    (net (code "31") (name "Net-(Q1-B)") (class "Default")
      (node (ref "Q1") (pin "1") (pinfunction "B_1") (pintype "passive"))
      (node (ref "R3") (pin "2") (pinfunction "2_2") (pintype "passive"))
    )
    (net (code "32") (name "Net-(Q2-B)") (class "Default")
      (node (ref "C12") (pin "1") (pinfunction "1_1") (pintype "passive"))
      (node (ref "Q2") (pin "1") (pinfunction "B_1") (pintype "passive"))
      (node (ref "R10") (pin "1") (pinfunction "1_1") (pintype "passive"))
    )
    (net (code "33") (name "Net-(Q2-C)") (class "Default")
      (node (ref "C15") (pin "2") (pinfunction "2_2") (pintype "passive"))
      (node (ref "Q2") (pin "3") (pinfunction "C_3") (pintype "passive"))
      (node (ref "Q3") (pin "1") (pinfunction "B_1") (pintype "passive"))
      (node (ref "R7") (pin "1") (pinfunction "1_1") (pintype "passive"))
    )
    (net (code "34") (name "Net-(Q2-E)") (class "Default")
      (node (ref "C13") (pin "+") (pinfunction "+_+") (pintype "passive"))
      (node (ref "Q2") (pin "2") (pinfunction "E_2") (pintype "passive"))
      (node (ref "R6") (pin "2") (pinfunction "2_2") (pintype "passive"))
      (node (ref "R8") (pin "1") (pinfunction "1_1") (pintype "passive"))
    )
    (net (code "35") (name "Net-(Q3-C)") (class "Default")
      (node (ref "C15") (pin "1") (pinfunction "1_1") (pintype "passive"))
      (node (ref "C16") (pin "+") (pinfunction "+_+") (pintype "passive"))
      (node (ref "Q3") (pin "3") (pinfunction "C_3") (pintype "passive"))
      (node (ref "R12") (pin "1") (pinfunction "1_1") (pintype "passive"))
      (node (ref "R8") (pin "2") (pinfunction "2_2") (pintype "passive"))
    )
    (net (code "36") (name "Net-(Q3-E)") (class "Default")
      (node (ref "C14") (pin "+") (pinfunction "+_+") (pintype "passive"))
      (node (ref "Q3") (pin "2") (pinfunction "E_2") (pintype "passive"))
      (node (ref "R9") (pin "2") (pinfunction "2_2") (pintype "passive"))
    )
    (net (code "37") (name "Net-(Q4-B)") (class "Default")
      (node (ref "C18") (pin "1") (pinfunction "1_1") (pintype "passive"))
      (node (ref "Q4") (pin "1") (pinfunction "B_1") (pintype "passive"))
      (node (ref "R17") (pin "1") (pinfunction "1_1") (pintype "passive"))
      (node (ref "R19") (pin "2") (pinfunction "2_2") (pintype "passive"))
    )
    (net (code "38") (name "Net-(Q4-C)") (class "Default")
      (node (ref "C21") (pin "+") (pinfunction "+_+") (pintype "passive"))
      (node (ref "C23") (pin "+") (pinfunction "+_+") (pintype "passive"))
      (node (ref "Q4") (pin "3") (pinfunction "C_3") (pintype "passive"))
      (node (ref "R18") (pin "1") (pinfunction "1_1") (pintype "passive"))
    )
    (net (code "39") (name "Net-(Q4-E)") (class "Default")
      (node (ref "C22") (pin "+") (pinfunction "+_+") (pintype "passive"))
      (node (ref "Q4") (pin "2") (pinfunction "E_2") (pintype "passive"))
      (node (ref "R20") (pin "2") (pinfunction "2_2") (pintype "passive"))
    )
    (net (code "40") (name "Net-(R10-Pad2)") (class "Default")
      (node (ref "R10") (pin "2") (pinfunction "2_2") (pintype "passive"))
      (node (ref "R11") (pin "2") (pinfunction "2_2") (pintype "passive"))
      (node (ref "R9") (pin "1") (pinfunction "1_1") (pintype "passive"))
    )
    (net (code "41") (name "Net-(R16-Pad1)") (class "Default")
      (node (ref "R16") (pin "1") (pinfunction "1_1") (pintype "passive"))
      (node (ref "TREBLE") (pin "2") (pinfunction "2_2") (pintype "passive"))
    )
    (net (code "42") (name "Net-(REG1-OUTPUT)") (class "Default")
      (node (ref "C7") (pin "1") (pinfunction "1_1") (pintype "passive"))
      (node (ref "C8") (pin "+") (pinfunction "+_+") (pintype "passive"))
      (node (ref "C9") (pin "1") (pinfunction "1_1") (pintype "passive"))
      (node (ref "REG1") (pin "1") (pinfunction "OUTPUT_1") (pintype "power_in"))
      (node (ref "U1") (pin "8") (pinfunction "VCC_8") (pintype "power_in"))
    )
    (net (code "43") (name "Vr") (class "Default")
      (node (ref "C3") (pin "1") (pinfunction "1_1") (pintype "passive"))
      (node (ref "C4") (pin "+") (pinfunction "+_+") (pintype "passive"))
      (node (ref "D2") (pin "1") (pinfunction "1_1") (pintype "passive"))
      (node (ref "R1") (pin "2") (pinfunction "2_2") (pintype "passive"))
      (node (ref "R12") (pin "2") (pinfunction "2_2") (pintype "passive"))
      (node (ref "R17") (pin "2") (pinfunction "2_2") (pintype "passive"))
      (node (ref "R18") (pin "2") (pinfunction "2_2") (pintype "passive"))
      (node (ref "R7") (pin "2") (pinfunction "2_2") (pintype "passive"))
    )
    (net (code "44") (name "unconnected-(IC1-CAP--Pad4)") (class "Default")
      (node (ref "IC1") (pin "4") (pinfunction "CAP-_4") (pintype "passive"))
    )
    (net (code "45") (name "unconnected-(IC1-LV-Pad6)") (class "Default")
      (node (ref "IC1") (pin "6") (pinfunction "LV_6") (pintype "passive"))
    )
    (net (code "46") (name "unconnected-(IC1-OSC-Pad7)") (class "Default")
      (node (ref "IC1") (pin "7") (pinfunction "OSC_7") (pintype "output"))
    )
    (net (code "47") (name "unconnected-(INPUT-PadR)") (class "Default")
      (node (ref "INPUT") (pin "R") (pinfunction "R_R") (pintype "passive+no_connect"))
    )
    (net (code "48") (name "unconnected-(OUTPUT-PadR)") (class "Default")
      (node (ref "OUTPUT") (pin "R") (pinfunction "R_R") (pintype "passive+no_connect"))
    )
  )
)
